# Sheet_1_2023-06-10.net
KiCad netlist of a schematic drawn in Altium Designer
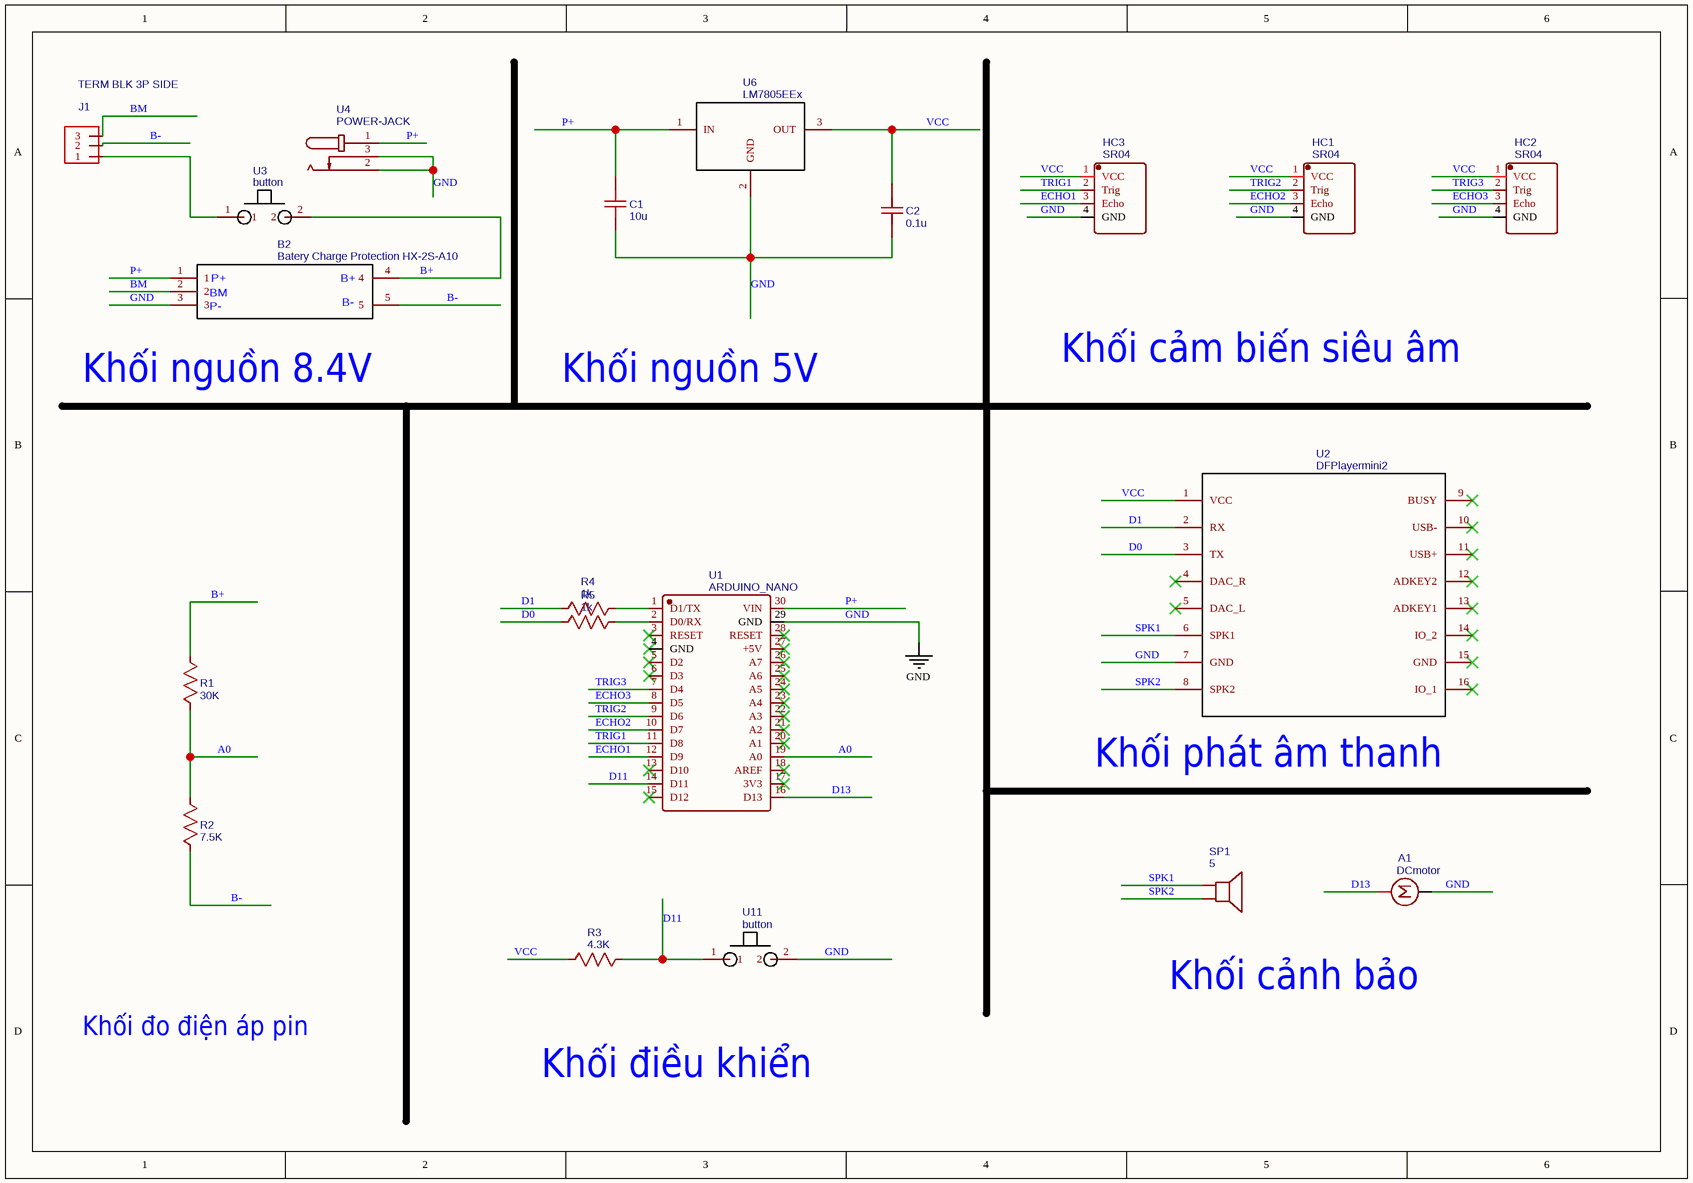
[diagram p0: Sheet_1_2023-06-10.schdoc]

(export (version "E")
  (design (tool "Eeschema 10.0.6"))
  (components
    (comp (ref "A1")
      (value "DCmotor")
      (fields (field (name "CONTRIBUTOR") "TONG JIAO"))
      (libsource (lib "altium-import") (part "root_0_DCmotor_"))
    )
    (comp (ref "B2")
      (value "Batery Charge Protection HX-2S-A10")
      (fields
        (field (name "BOM_MANUFACTURER PART") "HX-2S-A10")
        (field (name "CONTRIBUTOR") "VicenteOliverio")
      )
      (libsource (lib "altium-import") (part "root_0_Batery Charge Protection HX-2S-A10_"))
    )
    (comp (ref "C1")
      (value "10u")
      (fields (field (name "CONTRIBUTOR") "LCEDA_Lib"))
      (libsource (lib "altium-import") (part "root_1_10u_"))
    )
    (comp (ref "C2")
      (value "0.1u")
      (fields (field (name "CONTRIBUTOR") "LCEDA_Lib"))
      (libsource (lib "altium-import") (part "root_1_0.1u_"))
    )
    (comp (ref "HC1") (value "SR04") (libsource (lib "altium-import") (part "root_0_SR04_")))
    (comp (ref "HC2") (value "SR04") (libsource (lib "altium-import") (part "root_0_SR04_")))
    (comp (ref "HC3") (value "SR04") (libsource (lib "altium-import") (part "root_0_SR04_")))
    (comp (ref "J1")
      (value "TERM BLK 3P SIDE")
      (fields (field (name "BOM_SUPPLIER PART") "1725669") (field (name "CONTRIBUTOR") "grodda"))
      (libsource (lib "altium-import") (part "root_2_TERM BLK 3P SIDE_"))
    )
    (comp (ref "R1")
      (value "30K")
      (fields (field (name "CONTRIBUTOR") "LCEDA_Lib"))
      (libsource (lib "altium-import") (part "root_1_30K_"))
    )
    (comp (ref "R2")
      (value "7.5K")
      (fields (field (name "CONTRIBUTOR") "LCEDA_Lib"))
      (libsource (lib "altium-import") (part "root_1_7.5K_"))
    )
    (comp (ref "R3")
      (value "4.3K")
      (fields (field (name "CONTRIBUTOR") "LCEDA_Lib"))
      (libsource (lib "altium-import") (part "root_0_4.3K_"))
    )
    (comp (ref "R4")
      (value "1k")
      (fields (field (name "CONTRIBUTOR") "LCEDA_Lib"))
      (libsource (lib "altium-import") (part "root_0_1k_"))
    )
    (comp (ref "R5")
      (value "1k")
      (fields (field (name "CONTRIBUTOR") "LCEDA_Lib"))
      (libsource (lib "altium-import") (part "root_0_1k_"))
    )
    (comp (ref "SP1")
      (value "5")
      (fields (field (name "CONTRIBUTOR") "maximus250372"))
      (libsource (lib "altium-import") (part "root_0_5_"))
    )
    (comp (ref "U1")
      (value "ARDUINO_NANO")
      (fields (field (name "BOM_SUPPLIER PART") "C9900017879") (field (name "CONTRIBUTOR") "lcsc"))
      (libsource (lib "altium-import") (part "root_0_ARDUINO_NANO_"))
    )
    (comp (ref "U2")
      (value "DFPlayermini2")
      (fields (field (name "BOM_MANUFACTURER PART") "DFPlayer mini") (field (name "CONTRIBUTOR") "jonithan"))
      (libsource (lib "altium-import") (part "root_0_DFPlayermini2_"))
    )
    (comp (ref "U3")
      (value "button")
      (fields (field (name "CONTRIBUTOR") "visal"))
      (libsource (lib "altium-import") (part "root_0_button_"))
    )
    (comp (ref "U4")
      (value "POWER-JACK")
      (fields (field (name "BOM_SUPPLIER PART") "C9900001795") (field (name "CONTRIBUTOR") "LCSC"))
      (libsource (lib "altium-import") (part "root_0_POWER-JACK_"))
    )
    (comp (ref "U6")
      (value "LM7805EEx")
      (fields (field (name "CONTRIBUTOR") "artur2000"))
      (libsource (lib "altium-import") (part "root_0_LM7805EEx_"))
    )
    (comp (ref "U11")
      (value "button")
      (fields (field (name "CONTRIBUTOR") "visal"))
      (libsource (lib "altium-import") (part "root_0_button_"))
    )
  )
  (nets
    (net (code "1") (name "/A0") (class "Default")
      (node (ref "R1") (pin "1") (pinfunction "1_1") (pintype "passive"))
      (node (ref "R2") (pin "2") (pinfunction "2_2") (pintype "passive"))
      (node (ref "U1") (pin "19") (pinfunction "A0_19") (pintype "passive"))
    )
    (net (code "2") (name "/B+") (class "Default")
      (node (ref "B2") (pin "4") (pinfunction "4_4") (pintype "passive"))
      (node (ref "R1") (pin "2") (pinfunction "2_2") (pintype "passive"))
      (node (ref "U3") (pin "2") (pinfunction "2_2") (pintype "passive"))
    )
    (net (code "3") (name "/B-") (class "Default")
      (node (ref "B2") (pin "5") (pinfunction "5_5") (pintype "passive"))
      (node (ref "J1") (pin "2") (pinfunction "2_2") (pintype "passive"))
      (node (ref "R2") (pin "1") (pinfunction "1_1") (pintype "passive"))
    )
    (net (code "4") (name "/BM") (class "Default")
      (node (ref "B2") (pin "2") (pinfunction "2_2") (pintype "passive"))
      (node (ref "J1") (pin "3") (pinfunction "3_3") (pintype "passive"))
    )
    (net (code "5") (name "/D0") (class "Default")
      (node (ref "R5") (pin "1") (pinfunction "1_1") (pintype "passive"))
      (node (ref "U2") (pin "3") (pinfunction "TX_3") (pintype "passive"))
    )
    (net (code "6") (name "/D1") (class "Default")
      (node (ref "R4") (pin "1") (pinfunction "1_1") (pintype "passive"))
      (node (ref "U2") (pin "2") (pinfunction "RX_2") (pintype "passive"))
    )
    (net (code "7") (name "/D11") (class "Default")
      (node (ref "R3") (pin "2") (pinfunction "2_2") (pintype "passive"))
      (node (ref "U1") (pin "14") (pinfunction "D11_14") (pintype "passive"))
      (node (ref "U11") (pin "1") (pinfunction "1_1") (pintype "passive"))
    )
    (net (code "8") (name "/D13") (class "Default")
      (node (ref "A1") (pin "1") (pinfunction "+_1") (pintype "passive"))
      (node (ref "U1") (pin "16") (pinfunction "D13_16") (pintype "passive"))
    )
    (net (code "9") (name "/ECHO1") (class "Default")
      (node (ref "HC3") (pin "3") (pinfunction "Echo_3") (pintype "passive"))
      (node (ref "U1") (pin "12") (pinfunction "D9_12") (pintype "passive"))
    )
    (net (code "10") (name "/ECHO2") (class "Default")
      (node (ref "HC1") (pin "3") (pinfunction "Echo_3") (pintype "passive"))
      (node (ref "U1") (pin "10") (pinfunction "D7_10") (pintype "passive"))
    )
    (net (code "11") (name "/ECHO3") (class "Default")
      (node (ref "HC2") (pin "3") (pinfunction "Echo_3") (pintype "passive"))
      (node (ref "U1") (pin "8") (pinfunction "D5_8") (pintype "passive"))
    )
    (net (code "12") (name "/P+") (class "Default")
      (node (ref "B2") (pin "1") (pinfunction "1_1") (pintype "passive"))
      (node (ref "C1") (pin "2") (pinfunction "2_2") (pintype "passive"))
      (node (ref "U1") (pin "30") (pinfunction "VIN_30") (pintype "passive"))
      (node (ref "U4") (pin "1") (pinfunction "1_1") (pintype "passive"))
      (node (ref "U6") (pin "1") (pinfunction "IN_1") (pintype "passive"))
    )
    (net (code "13") (name "/SPK1") (class "Default")
      (node (ref "SP1") (pin "1") (pinfunction "+_1") (pintype "passive"))
      (node (ref "U2") (pin "6") (pinfunction "SPK1_6") (pintype "passive"))
    )
    (net (code "14") (name "/SPK2") (class "Default")
      (node (ref "SP1") (pin "2") (pinfunction "-_2") (pintype "passive"))
      (node (ref "U2") (pin "8") (pinfunction "SPK2_8") (pintype "passive"))
    )
    (net (code "15") (name "/TRIG1") (class "Default")
      (node (ref "HC3") (pin "2") (pinfunction "Trig_2") (pintype "passive"))
      (node (ref "U1") (pin "11") (pinfunction "D8_11") (pintype "passive"))
    )
    (net (code "16") (name "/TRIG2") (class "Default")
      (node (ref "HC1") (pin "2") (pinfunction "Trig_2") (pintype "passive"))
      (node (ref "U1") (pin "9") (pinfunction "D6_9") (pintype "passive"))
    )
    (net (code "17") (name "/TRIG3") (class "Default")
      (node (ref "HC2") (pin "2") (pinfunction "Trig_2") (pintype "passive"))
      (node (ref "U1") (pin "7") (pinfunction "D4_7") (pintype "passive"))
    )
    (net (code "18") (name "/VCC") (class "Default")
      (node (ref "C2") (pin "2") (pinfunction "2_2") (pintype "passive"))
      (node (ref "HC1") (pin "1") (pinfunction "VCC_1") (pintype "passive"))
      (node (ref "HC2") (pin "1") (pinfunction "VCC_1") (pintype "passive"))
      (node (ref "HC3") (pin "1") (pinfunction "VCC_1") (pintype "passive"))
      (node (ref "R3") (pin "1") (pinfunction "1_1") (pintype "passive"))
      (node (ref "U2") (pin "1") (pinfunction "VCC_1") (pintype "passive"))
      (node (ref "U6") (pin "3") (pinfunction "OUT_3") (pintype "passive"))
    )
    (net (code "19") (name "GND") (class "Default")
      (node (ref "A1") (pin "2") (pinfunction "2_2") (pintype "passive"))
      (node (ref "B2") (pin "3") (pinfunction "3_3") (pintype "passive"))
      (node (ref "C1") (pin "1") (pinfunction "1_1") (pintype "passive"))
      (node (ref "C2") (pin "1") (pinfunction "1_1") (pintype "passive"))
      (node (ref "HC1") (pin "4") (pinfunction "GND_4") (pintype "passive"))
      (node (ref "HC2") (pin "4") (pinfunction "GND_4") (pintype "passive"))
      (node (ref "HC3") (pin "4") (pinfunction "GND_4") (pintype "passive"))
      (node (ref "U1") (pin "29") (pinfunction "GND_29") (pintype "passive"))
      (node (ref "U11") (pin "2") (pinfunction "2_2") (pintype "passive"))
      (node (ref "U2") (pin "7") (pinfunction "GND_7") (pintype "passive"))
      (node (ref "U4") (pin "2") (pinfunction "2_2") (pintype "passive"))
      (node (ref "U4") (pin "3") (pinfunction "3_3") (pintype "passive"))
      (node (ref "U6") (pin "2") (pinfunction "GND_2") (pintype "passive"))
    )
    (net (code "20") (name "Net-(J1-Pad1)") (class "Default")
      (node (ref "J1") (pin "1") (pinfunction "1_1") (pintype "passive"))
      (node (ref "U3") (pin "1") (pinfunction "1_1") (pintype "passive"))
    )
    (net (code "21") (name "Net-(U1-D0{slash}RX)") (class "Default")
      (node (ref "R5") (pin "2") (pinfunction "2_2") (pintype "passive"))
      (node (ref "U1") (pin "2") (pinfunction "D0/RX_2") (pintype "passive"))
    )
    (net (code "22") (name "Net-(U1-D1{slash}TX)") (class "Default")
      (node (ref "R4") (pin "2") (pinfunction "2_2") (pintype "passive"))
      (node (ref "U1") (pin "1") (pinfunction "D1/TX_1") (pintype "passive"))
    )
    (net (code "23") (name "unconnected-(U1-+5V-Pad27)") (class "Default")
      (node (ref "U1") (pin "27") (pinfunction "+5V_27") (pintype "passive+no_connect"))
    )
    (net (code "24") (name "unconnected-(U1-3V3-Pad17)") (class "Default")
      (node (ref "U1") (pin "17") (pinfunction "3V3_17") (pintype "passive+no_connect"))
    )
    (net (code "25") (name "unconnected-(U1-A1-Pad20)") (class "Default")
      (node (ref "U1") (pin "20") (pinfunction "A1_20") (pintype "passive+no_connect"))
    )
    (net (code "26") (name "unconnected-(U1-A2-Pad21)") (class "Default")
      (node (ref "U1") (pin "21") (pinfunction "A2_21") (pintype "passive+no_connect"))
    )
    (net (code "27") (name "unconnected-(U1-A3-Pad22)") (class "Default")
      (node (ref "U1") (pin "22") (pinfunction "A3_22") (pintype "passive+no_connect"))
    )
    (net (code "28") (name "unconnected-(U1-A4-Pad23)") (class "Default")
      (node (ref "U1") (pin "23") (pinfunction "A4_23") (pintype "passive+no_connect"))
    )
    (net (code "29") (name "unconnected-(U1-A5-Pad24)") (class "Default")
      (node (ref "U1") (pin "24") (pinfunction "A5_24") (pintype "passive+no_connect"))
    )
    (net (code "30") (name "unconnected-(U1-A6-Pad25)") (class "Default")
      (node (ref "U1") (pin "25") (pinfunction "A6_25") (pintype "passive+no_connect"))
    )
    (net (code "31") (name "unconnected-(U1-A7-Pad26)") (class "Default")
      (node (ref "U1") (pin "26") (pinfunction "A7_26") (pintype "passive+no_connect"))
    )
    (net (code "32") (name "unconnected-(U1-AREF-Pad18)") (class "Default")
      (node (ref "U1") (pin "18") (pinfunction "AREF_18") (pintype "passive+no_connect"))
    )
    (net (code "33") (name "unconnected-(U1-D2-Pad5)") (class "Default")
      (node (ref "U1") (pin "5") (pinfunction "D2_5") (pintype "passive+no_connect"))
    )
    (net (code "34") (name "unconnected-(U1-D3-Pad6)") (class "Default")
      (node (ref "U1") (pin "6") (pinfunction "D3_6") (pintype "passive+no_connect"))
    )
    (net (code "35") (name "unconnected-(U1-D10-Pad13)") (class "Default")
      (node (ref "U1") (pin "13") (pinfunction "D10_13") (pintype "passive+no_connect"))
    )
    (net (code "36") (name "unconnected-(U1-D12-Pad15)") (class "Default")
      (node (ref "U1") (pin "15") (pinfunction "D12_15") (pintype "passive+no_connect"))
    )
    (net (code "37") (name "unconnected-(U1-GND-Pad4)") (class "Default")
      (node (ref "U1") (pin "4") (pinfunction "GND_4") (pintype "passive+no_connect"))
    )
    (net (code "38") (name "unconnected-(U1-RESET-Pad3)") (class "Default")
      (node (ref "U1") (pin "3") (pinfunction "RESET_3") (pintype "passive+no_connect"))
    )
    (net (code "39") (name "unconnected-(U1-RESET-Pad28)") (class "Default")
      (node (ref "U1") (pin "28") (pinfunction "RESET_28") (pintype "passive+no_connect"))
    )
    (net (code "40") (name "unconnected-(U2-ADKEY1-Pad13)") (class "Default")
      (node (ref "U2") (pin "13") (pinfunction "ADKEY1_13") (pintype "passive+no_connect"))
    )
    (net (code "41") (name "unconnected-(U2-ADKEY2-Pad12)") (class "Default")
      (node (ref "U2") (pin "12") (pinfunction "ADKEY2_12") (pintype "passive+no_connect"))
    )
    (net (code "42") (name "unconnected-(U2-BUSY-Pad9)") (class "Default")
      (node (ref "U2") (pin "9") (pinfunction "BUSY_9") (pintype "passive+no_connect"))
    )
    (net (code "43") (name "unconnected-(U2-DAC_L-Pad5)") (class "Default")
      (node (ref "U2") (pin "5") (pinfunction "DAC_L_5") (pintype "passive+no_connect"))
    )
    (net (code "44") (name "unconnected-(U2-DAC_R-Pad4)") (class "Default")
      (node (ref "U2") (pin "4") (pinfunction "DAC_R_4") (pintype "passive+no_connect"))
    )
    (net (code "45") (name "unconnected-(U2-GND-Pad15)") (class "Default")
      (node (ref "U2") (pin "15") (pinfunction "GND_15") (pintype "passive+no_connect"))
    )
    (net (code "46") (name "unconnected-(U2-IO_1-Pad16)") (class "Default")
      (node (ref "U2") (pin "16") (pinfunction "IO_1_16") (pintype "passive+no_connect"))
    )
    (net (code "47") (name "unconnected-(U2-IO_2-Pad14)") (class "Default")
      (node (ref "U2") (pin "14") (pinfunction "IO_2_14") (pintype "passive+no_connect"))
    )
    (net (code "48") (name "unconnected-(U2-USB+-Pad11)") (class "Default")
      (node (ref "U2") (pin "11") (pinfunction "USB+_11") (pintype "passive+no_connect"))
    )
    (net (code "49") (name "unconnected-(U2-USB--Pad10)") (class "Default")
      (node (ref "U2") (pin "10") (pinfunction "USB-_10") (pintype "passive+no_connect"))
    )
  )
)
